# 02_Mcu.net
KiCad netlist of a schematic drawn in Altium Designer
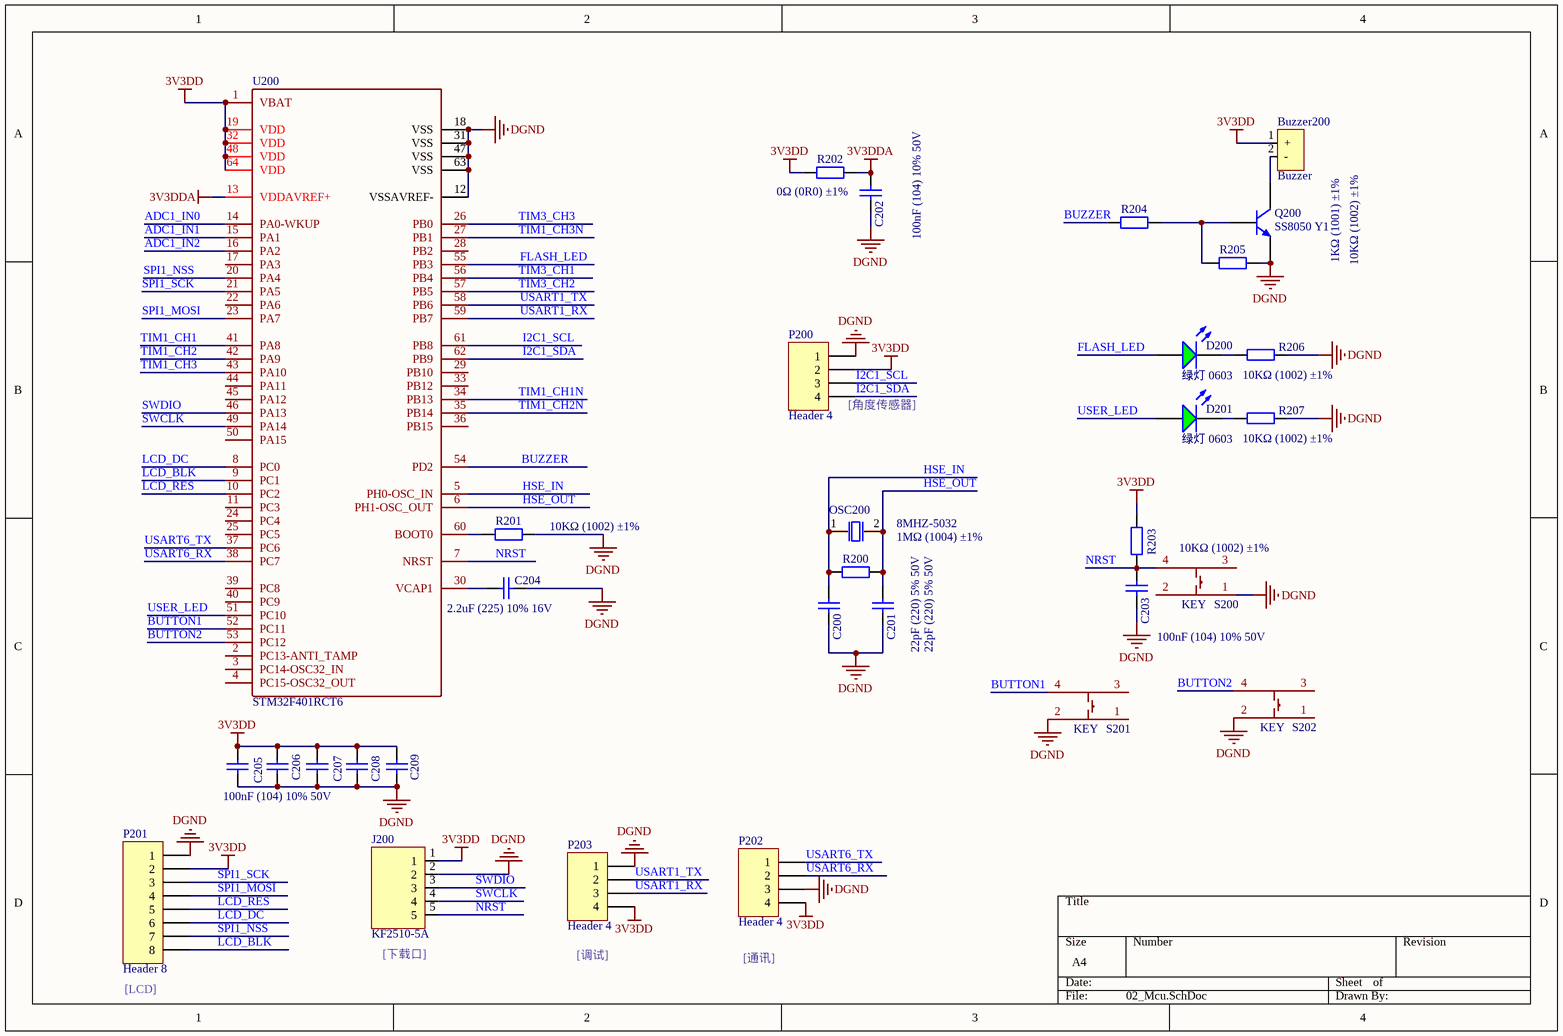
[diagram p0: 02_Mcu.SchDoc]

(export (version "E")
  (design (tool "Eeschema 10.0.6"))
  (components
    (comp (ref "Buzzer200")
      (value "Buzzer")
      (footprint "buzzer-0905")
      (libsource (lib "Schlibv2") (part "Buzzer"))
    )
    (comp (ref "C200")
      (value "22pF (220) 5% 50V")
      (footprint "0603_C")
      (description "贴片电容")
      (libsource (lib "Miscellaneous Devices LC") (part "0603 22pF (220) 5% 50V"))
    )
    (comp (ref "C201")
      (value "22pF (220) 5% 50V")
      (footprint "0603_C")
      (description "贴片电容")
      (libsource (lib "Miscellaneous Devices LC") (part "0603 22pF (220) 5% 50V"))
    )
    (comp (ref "C202")
      (value "100nF (104) 10% 50V")
      (footprint "0603_C")
      (description "贴片电容")
      (libsource (lib "Miscellaneous Devices LC") (part "0603 100nF (104) 10% 50V"))
    )
    (comp (ref "C203")
      (value "100nF (104) 10% 50V")
      (footprint "0603_C")
      (description "贴片电容")
      (libsource (lib "Miscellaneous Devices LC") (part "0603 100nF (104) 10% 50V"))
    )
    (comp (ref "C204")
      (value "2.2uF (225) 10% 16V")
      (footprint "0603_C")
      (description "贴片电容")
      (libsource (lib "Miscellaneous Devices LC") (part "0603 2.2uF (225) 10% 16V"))
    )
    (comp (ref "C205")
      (value "100nF (104) 10% 50V")
      (footprint "LC-0603_C")
      (description "贴片电容")
      (libsource (lib "Miscellaneous Devices LC") (part "0603 100nF (104) 10% 50V"))
    )
    (comp (ref "C206")
      (value "100nF (104) 10% 50V")
      (footprint "LC-0603_C")
      (description "贴片电容")
      (libsource (lib "Miscellaneous Devices LC") (part "0603 100nF (104) 10% 50V"))
    )
    (comp (ref "C207")
      (value "100nF (104) 10% 50V")
      (footprint "LC-0603_C")
      (description "贴片电容")
      (libsource (lib "Miscellaneous Devices LC") (part "0603 100nF (104) 10% 50V"))
    )
    (comp (ref "C208")
      (value "100nF (104) 10% 50V")
      (footprint "LC-0603_C")
      (description "贴片电容")
      (libsource (lib "Miscellaneous Devices LC") (part "0603 100nF (104) 10% 50V"))
    )
    (comp (ref "C209")
      (value "100nF (104) 10% 50V")
      (footprint "LC-0603_C")
      (description "贴片电容")
      (libsource (lib "Miscellaneous Devices LC") (part "0603 100nF (104) 10% 50V"))
    )
    (comp (ref "D200")
      (value "绿灯 0603")
      (footprint "0603_LED_S1")
      (description "发光二极管")
      (libsource (lib "Miscellaneous Devices LC") (part "0603 绿灯"))
    )
    (comp (ref "D201")
      (value "绿灯 0603")
      (footprint "0603_LED_S1")
      (description "发光二极管")
      (libsource (lib "Miscellaneous Devices LC") (part "0603 绿灯"))
    )
    (comp (ref "J200")
      (value "KF2510-5A")
      (footprint "KF2510-5A")
      (libsource (lib "Schlibv2") (part "KF2510-5A"))
    )
    (comp (ref "OSC200")
      (value "8MHZ-5032")
      (footprint "8MHZ-5032")
      (libsource (lib "Schlibv2") (part "8MHZ-5032"))
    )
    (comp (ref "P200")
      (value "Header 4")
      (footprint "HDR1X4")
      (description "Header, 4-Pin")
      (fields (field (name "PUBLISHER") "Altium Limited"))
      (libsource (lib "Miscellaneous Connectors") (part "Header 4"))
    )
    (comp (ref "P201")
      (value "Header 8")
      (footprint "HDR1X8")
      (description "Header, 8-Pin")
      (fields (field (name "PUBLISHER") "Altium Limited"))
      (libsource (lib "Miscellaneous Connectors") (part "Header 8"))
    )
    (comp (ref "P202")
      (value "Header 4")
      (footprint "HDR1X4")
      (description "Header, 4-Pin")
      (fields (field (name "PUBLISHER") "Altium Limited"))
      (libsource (lib "Miscellaneous Connectors") (part "Header 4"))
    )
    (comp (ref "P203")
      (value "Header 4")
      (footprint "HDR1X4")
      (description "Header, 4-Pin")
      (fields (field (name "PUBLISHER") "Altium Limited"))
      (libsource (lib "Miscellaneous Connectors") (part "Header 4"))
    )
    (comp (ref "Q200")
      (value "SS8050 Y1")
      (footprint "SOT-23(SOT-23-3)")
      (description "三极管")
      (libsource (lib "Miscellaneous Devices LC") (part "SOT-23 SS8050 Y1"))
    )
    (comp (ref "R200")
      (value "1MΩ (1004) ±1%")
      (footprint "0603_R")
      (description "贴片电阻")
      (libsource (lib "Miscellaneous Devices LC") (part "0603 1MΩ (1004) 1%"))
    )
    (comp (ref "R201")
      (value "10KΩ (1002) ±1%")
      (footprint "0603_R")
      (description "贴片电阻")
      (libsource (lib "") (part "0603 10KΩ (1002) 1%_1"))
    )
    (comp (ref "R202")
      (value "0Ω (0R0) ±1%")
      (footprint "0603_R")
      (description "贴片电阻")
      (libsource (lib "Miscellaneous Devices LC") (part "0603 0Ω (0R0) 1%"))
    )
    (comp (ref "R203")
      (value "10KΩ (1002) ±1%")
      (footprint "0603_R")
      (description "贴片电阻")
      (libsource (lib "Miscellaneous Devices LC") (part "0603 10KΩ (1002) 1%"))
    )
    (comp (ref "R204")
      (value "1KΩ (1001) ±1%")
      (footprint "0603_R")
      (description "贴片电阻")
      (libsource (lib "Miscellaneous Devices LC") (part "0603 1KΩ (1001) 1%"))
    )
    (comp (ref "R205")
      (value "10KΩ (1002) ±1%")
      (footprint "0603_R")
      (description "贴片电阻")
      (libsource (lib "") (part "0603 10KΩ (1002) 1%_1"))
    )
    (comp (ref "R206")
      (value "10KΩ (1002) ±1%")
      (footprint "0603_R")
      (description "贴片电阻")
      (libsource (lib "") (part "0603 10KΩ (1002) 1%_1"))
    )
    (comp (ref "R207")
      (value "10KΩ (1002) ±1%")
      (footprint "0603_R")
      (description "贴片电阻")
      (libsource (lib "") (part "0603 10KΩ (1002) 1%_1"))
    )
    (comp (ref "S200")
      (value "KEY")
      (footprint "KEY_WHITE")
      (description "白色方块")
      (libsource (lib "Schlibv2") (part "KEY"))
    )
    (comp (ref "S201")
      (value "KEY")
      (footprint "KEY_WHITE")
      (description "白色方块")
      (libsource (lib "Schlibv2") (part "KEY"))
    )
    (comp (ref "S202")
      (value "KEY")
      (footprint "KEY_WHITE")
      (description "白色方块")
      (libsource (lib "Schlibv2") (part "KEY"))
    )
    (comp (ref "U200")
      (value "STM32F401RCT6")
      (footprint "STM32F401RCT6")
      (libsource (lib "Schlibv2") (part "STM32F401RCT6"))
    )
  )
  (nets
    (net (code "1") (name "/ADC1_IN0") (class "Default")
      (node (ref "U200") (pin "14") (pinfunction "PA0-WKUP_14") (pintype "passive"))
    )
    (net (code "2") (name "/ADC1_IN1") (class "Default")
      (node (ref "U200") (pin "15") (pinfunction "PA1_15") (pintype "passive"))
    )
    (net (code "3") (name "/ADC1_IN2") (class "Default")
      (node (ref "U200") (pin "16") (pinfunction "PA2_16") (pintype "passive"))
    )
    (net (code "4") (name "/BUTTON1") (class "Default")
      (node (ref "S201") (pin "4") (pinfunction "4_4") (pintype "passive"))
      (node (ref "U200") (pin "52") (pinfunction "PC11_52") (pintype "passive"))
    )
    (net (code "5") (name "/BUTTON2") (class "Default")
      (node (ref "S202") (pin "4") (pinfunction "4_4") (pintype "passive"))
      (node (ref "U200") (pin "53") (pinfunction "PC12_53") (pintype "passive"))
    )
    (net (code "6") (name "/BUZZER") (class "Default")
      (node (ref "R204") (pin "1") (pinfunction "1_1") (pintype "passive"))
      (node (ref "U200") (pin "54") (pinfunction "PD2_54") (pintype "passive"))
    )
    (net (code "7") (name "/FLASH_LED") (class "Default")
      (node (ref "D200") (pin "A") (pinfunction "A_A") (pintype "passive"))
      (node (ref "U200") (pin "55") (pinfunction "PB3_55") (pintype "passive"))
    )
    (net (code "8") (name "/HSE_IN") (class "Default")
      (node (ref "C200") (pin "2") (pinfunction "2_2") (pintype "passive"))
      (node (ref "OSC200") (pin "1") (pinfunction "OSC1_1") (pintype "passive"))
      (node (ref "R200") (pin "1") (pinfunction "1_1") (pintype "passive"))
      (node (ref "U200") (pin "5") (pinfunction "PH0-OSC_IN_5") (pintype "passive"))
    )
    (net (code "9") (name "/HSE_OUT") (class "Default")
      (node (ref "C201") (pin "2") (pinfunction "2_2") (pintype "passive"))
      (node (ref "OSC200") (pin "2") (pinfunction "OSC2_2") (pintype "passive"))
      (node (ref "R200") (pin "2") (pinfunction "2_2") (pintype "passive"))
      (node (ref "U200") (pin "6") (pinfunction "PH1-OSC_OUT_6") (pintype "passive"))
    )
    (net (code "10") (name "/I2C1_SCL") (class "Default")
      (node (ref "P200") (pin "3") (pinfunction "3_3") (pintype "passive"))
      (node (ref "U200") (pin "61") (pinfunction "PB8_61") (pintype "passive"))
    )
    (net (code "11") (name "/I2C1_SDA") (class "Default")
      (node (ref "P200") (pin "4") (pinfunction "4_4") (pintype "passive"))
      (node (ref "U200") (pin "62") (pinfunction "PB9_62") (pintype "passive"))
    )
    (net (code "12") (name "/LCD_BLK") (class "Default")
      (node (ref "P201") (pin "8") (pinfunction "8_8") (pintype "passive"))
      (node (ref "U200") (pin "9") (pinfunction "PC1_9") (pintype "passive"))
    )
    (net (code "13") (name "/LCD_DC") (class "Default")
      (node (ref "P201") (pin "6") (pinfunction "6_6") (pintype "passive"))
      (node (ref "U200") (pin "8") (pinfunction "PC0_8") (pintype "passive"))
    )
    (net (code "14") (name "/LCD_RES") (class "Default")
      (node (ref "P201") (pin "5") (pinfunction "5_5") (pintype "passive"))
      (node (ref "U200") (pin "10") (pinfunction "PC2_10") (pintype "passive"))
    )
    (net (code "15") (name "/NRST") (class "Default")
      (node (ref "C203") (pin "2") (pinfunction "2_2") (pintype "passive"))
      (node (ref "J200") (pin "5") (pinfunction "5_5") (pintype "passive"))
      (node (ref "R203") (pin "1") (pinfunction "1_1") (pintype "passive"))
      (node (ref "S200") (pin "4") (pinfunction "4_4") (pintype "passive"))
      (node (ref "U200") (pin "7") (pinfunction "NRST_7") (pintype "passive"))
    )
    (net (code "16") (name "/SPI1_MOSI") (class "Default")
      (node (ref "P201") (pin "4") (pinfunction "4_4") (pintype "passive"))
      (node (ref "U200") (pin "23") (pinfunction "PA7_23") (pintype "passive"))
    )
    (net (code "17") (name "/SPI1_NSS") (class "Default")
      (node (ref "P201") (pin "7") (pinfunction "7_7") (pintype "passive"))
      (node (ref "U200") (pin "20") (pinfunction "PA4_20") (pintype "passive"))
    )
    (net (code "18") (name "/SPI1_SCK") (class "Default")
      (node (ref "P201") (pin "3") (pinfunction "3_3") (pintype "passive"))
      (node (ref "U200") (pin "21") (pinfunction "PA5_21") (pintype "passive"))
    )
    (net (code "19") (name "/SWCLK") (class "Default")
      (node (ref "J200") (pin "4") (pinfunction "4_4") (pintype "passive"))
      (node (ref "U200") (pin "49") (pinfunction "PA14_49") (pintype "passive"))
    )
    (net (code "20") (name "/SWDIO") (class "Default")
      (node (ref "J200") (pin "3") (pinfunction "3_3") (pintype "passive"))
      (node (ref "U200") (pin "46") (pinfunction "PA13_46") (pintype "passive"))
    )
    (net (code "21") (name "/TIM1_CH1") (class "Default")
      (node (ref "U200") (pin "41") (pinfunction "PA8_41") (pintype "passive"))
    )
    (net (code "22") (name "/TIM1_CH1N") (class "Default")
      (node (ref "U200") (pin "34") (pinfunction "PB13_34") (pintype "passive"))
    )
    (net (code "23") (name "/TIM1_CH2") (class "Default")
      (node (ref "U200") (pin "42") (pinfunction "PA9_42") (pintype "passive"))
    )
    (net (code "24") (name "/TIM1_CH2N") (class "Default")
      (node (ref "U200") (pin "35") (pinfunction "PB14_35") (pintype "passive"))
    )
    (net (code "25") (name "/TIM1_CH3") (class "Default")
      (node (ref "U200") (pin "43") (pinfunction "PA10_43") (pintype "passive"))
    )
    (net (code "26") (name "/TIM1_CH3N") (class "Default")
      (node (ref "U200") (pin "27") (pinfunction "PB1_27") (pintype "passive"))
    )
    (net (code "27") (name "/TIM3_CH1") (class "Default")
      (node (ref "U200") (pin "56") (pinfunction "PB4_56") (pintype "passive"))
    )
    (net (code "28") (name "/TIM3_CH2") (class "Default")
      (node (ref "U200") (pin "57") (pinfunction "PB5_57") (pintype "passive"))
    )
    (net (code "29") (name "/TIM3_CH3") (class "Default")
      (node (ref "U200") (pin "26") (pinfunction "PB0_26") (pintype "passive"))
    )
    (net (code "30") (name "/USART1_RX") (class "Default")
      (node (ref "P203") (pin "3") (pinfunction "3_3") (pintype "passive"))
      (node (ref "U200") (pin "59") (pinfunction "PB7_59") (pintype "passive"))
    )
    (net (code "31") (name "/USART1_TX") (class "Default")
      (node (ref "P203") (pin "2") (pinfunction "2_2") (pintype "passive"))
      (node (ref "U200") (pin "58") (pinfunction "PB6_58") (pintype "passive"))
    )
    (net (code "32") (name "/USART6_RX") (class "Default")
      (node (ref "P202") (pin "2") (pinfunction "2_2") (pintype "passive"))
      (node (ref "U200") (pin "38") (pinfunction "PC7_38") (pintype "passive"))
    )
    (net (code "33") (name "/USART6_TX") (class "Default")
      (node (ref "P202") (pin "1") (pinfunction "1_1") (pintype "passive"))
      (node (ref "U200") (pin "37") (pinfunction "PC6_37") (pintype "passive"))
    )
    (net (code "34") (name "/USER_LED") (class "Default")
      (node (ref "D201") (pin "A") (pinfunction "A_A") (pintype "passive"))
      (node (ref "U200") (pin "51") (pinfunction "PC10_51") (pintype "passive"))
    )
    (net (code "35") (name "3V3DD") (class "Default")
      (node (ref "Buzzer200") (pin "1") (pinfunction "+_1") (pintype "passive"))
      (node (ref "C205") (pin "2") (pinfunction "2_2") (pintype "passive"))
      (node (ref "C206") (pin "2") (pinfunction "2_2") (pintype "passive"))
      (node (ref "C207") (pin "2") (pinfunction "2_2") (pintype "passive"))
      (node (ref "C208") (pin "2") (pinfunction "2_2") (pintype "passive"))
      (node (ref "C209") (pin "2") (pinfunction "2_2") (pintype "passive"))
      (node (ref "J200") (pin "1") (pinfunction "1_1") (pintype "passive"))
      (node (ref "P200") (pin "2") (pinfunction "2_2") (pintype "passive"))
      (node (ref "P201") (pin "2") (pinfunction "2_2") (pintype "passive"))
      (node (ref "P202") (pin "4") (pinfunction "4_4") (pintype "passive"))
      (node (ref "P203") (pin "4") (pinfunction "4_4") (pintype "passive"))
      (node (ref "R202") (pin "1") (pinfunction "1_1") (pintype "passive"))
      (node (ref "R203") (pin "2") (pinfunction "2_2") (pintype "passive"))
      (node (ref "U200") (pin "1") (pinfunction "VBAT_1") (pintype "passive"))
      (node (ref "U200") (pin "19") (pinfunction "VDD_19") (pintype "passive"))
      (node (ref "U200") (pin "32") (pinfunction "VDD_32") (pintype "passive"))
      (node (ref "U200") (pin "48") (pinfunction "VDD_48") (pintype "passive"))
      (node (ref "U200") (pin "64") (pinfunction "VDD_64") (pintype "passive"))
    )
    (net (code "36") (name "3V3DDA") (class "Default")
      (node (ref "C202") (pin "2") (pinfunction "2_2") (pintype "passive"))
      (node (ref "R202") (pin "2") (pinfunction "2_2") (pintype "passive"))
      (node (ref "U200") (pin "13") (pinfunction "VDDAVREF+_13") (pintype "passive"))
    )
    (net (code "37") (name "DGND") (class "Default")
      (node (ref "C200") (pin "1") (pinfunction "1_1") (pintype "passive"))
      (node (ref "C201") (pin "1") (pinfunction "1_1") (pintype "passive"))
      (node (ref "C202") (pin "1") (pinfunction "1_1") (pintype "passive"))
      (node (ref "C203") (pin "1") (pinfunction "1_1") (pintype "passive"))
      (node (ref "C204") (pin "2") (pinfunction "2_2") (pintype "passive"))
      (node (ref "C205") (pin "1") (pinfunction "1_1") (pintype "passive"))
      (node (ref "C206") (pin "1") (pinfunction "1_1") (pintype "passive"))
      (node (ref "C207") (pin "1") (pinfunction "1_1") (pintype "passive"))
      (node (ref "C208") (pin "1") (pinfunction "1_1") (pintype "passive"))
      (node (ref "C209") (pin "1") (pinfunction "1_1") (pintype "passive"))
      (node (ref "J200") (pin "2") (pinfunction "2_2") (pintype "passive"))
      (node (ref "P200") (pin "1") (pinfunction "1_1") (pintype "passive"))
      (node (ref "P201") (pin "1") (pinfunction "1_1") (pintype "passive"))
      (node (ref "P202") (pin "3") (pinfunction "3_3") (pintype "passive"))
      (node (ref "P203") (pin "1") (pinfunction "1_1") (pintype "passive"))
      (node (ref "Q200") (pin "2") (pinfunction "E_2") (pintype "passive"))
      (node (ref "R201") (pin "2") (pinfunction "2_2") (pintype "passive"))
      (node (ref "R205") (pin "2") (pinfunction "2_2") (pintype "passive"))
      (node (ref "R206") (pin "2") (pinfunction "2_2") (pintype "passive"))
      (node (ref "R207") (pin "2") (pinfunction "2_2") (pintype "passive"))
      (node (ref "S200") (pin "1") (pinfunction "1_1") (pintype "passive"))
      (node (ref "S201") (pin "2") (pinfunction "2_2") (pintype "passive"))
      (node (ref "S202") (pin "2") (pinfunction "2_2") (pintype "passive"))
      (node (ref "U200") (pin "12") (pinfunction "VSSAVREF-_12") (pintype "passive"))
      (node (ref "U200") (pin "18") (pinfunction "VSS_18") (pintype "passive"))
      (node (ref "U200") (pin "31") (pinfunction "VSS_31") (pintype "passive"))
      (node (ref "U200") (pin "47") (pinfunction "VSS_47") (pintype "passive"))
      (node (ref "U200") (pin "63") (pinfunction "VSS_63") (pintype "passive"))
    )
    (net (code "38") (name "Net-(Buzzer200--)") (class "Default")
      (node (ref "Buzzer200") (pin "2") (pinfunction "-_2") (pintype "passive"))
      (node (ref "Q200") (pin "3") (pinfunction "C_3") (pintype "passive"))
    )
    (net (code "39") (name "Net-(D200-PadK)") (class "Default")
      (node (ref "D200") (pin "K") (pinfunction "K_K") (pintype "passive"))
      (node (ref "R206") (pin "1") (pinfunction "1_1") (pintype "passive"))
    )
    (net (code "40") (name "Net-(D201-PadK)") (class "Default")
      (node (ref "D201") (pin "K") (pinfunction "K_K") (pintype "passive"))
      (node (ref "R207") (pin "1") (pinfunction "1_1") (pintype "passive"))
    )
    (net (code "41") (name "Net-(Q200-B)") (class "Default")
      (node (ref "Q200") (pin "1") (pinfunction "B_1") (pintype "passive"))
      (node (ref "R204") (pin "2") (pinfunction "2_2") (pintype "passive"))
      (node (ref "R205") (pin "1") (pinfunction "1_1") (pintype "passive"))
    )
    (net (code "42") (name "Net-(U200-BOOT0)") (class "Default")
      (node (ref "R201") (pin "1") (pinfunction "1_1") (pintype "passive"))
      (node (ref "U200") (pin "60") (pinfunction "BOOT0_60") (pintype "passive"))
    )
    (net (code "43") (name "Net-(U200-VCAP1)") (class "Default")
      (node (ref "C204") (pin "1") (pinfunction "1_1") (pintype "passive"))
      (node (ref "U200") (pin "30") (pinfunction "VCAP1_30") (pintype "passive"))
    )
    (net (code "44") (name "unconnected-(S200-Pad2)") (class "Default")
      (node (ref "S200") (pin "2") (pinfunction "2_2") (pintype "passive"))
    )
    (net (code "45") (name "unconnected-(S200-Pad3)") (class "Default")
      (node (ref "S200") (pin "3") (pinfunction "3_3") (pintype "passive"))
    )
    (net (code "46") (name "unconnected-(S201-Pad1)") (class "Default")
      (node (ref "S201") (pin "1") (pinfunction "1_1") (pintype "passive"))
    )
    (net (code "47") (name "unconnected-(S201-Pad3)") (class "Default")
      (node (ref "S201") (pin "3") (pinfunction "3_3") (pintype "passive"))
    )
    (net (code "48") (name "unconnected-(S202-Pad1)") (class "Default")
      (node (ref "S202") (pin "1") (pinfunction "1_1") (pintype "passive"))
    )
    (net (code "49") (name "unconnected-(S202-Pad3)") (class "Default")
      (node (ref "S202") (pin "3") (pinfunction "3_3") (pintype "passive"))
    )
    (net (code "50") (name "unconnected-(U200-PA3-Pad17)") (class "Default")
      (node (ref "U200") (pin "17") (pinfunction "PA3_17") (pintype "passive"))
    )
    (net (code "51") (name "unconnected-(U200-PA6-Pad22)") (class "Default")
      (node (ref "U200") (pin "22") (pinfunction "PA6_22") (pintype "passive"))
    )
    (net (code "52") (name "unconnected-(U200-PA11-Pad44)") (class "Default")
      (node (ref "U200") (pin "44") (pinfunction "PA11_44") (pintype "passive"))
    )
    (net (code "53") (name "unconnected-(U200-PA12-Pad45)") (class "Default")
      (node (ref "U200") (pin "45") (pinfunction "PA12_45") (pintype "passive"))
    )
    (net (code "54") (name "unconnected-(U200-PA15-Pad50)") (class "Default")
      (node (ref "U200") (pin "50") (pinfunction "PA15_50") (pintype "passive"))
    )
    (net (code "55") (name "unconnected-(U200-PB2-Pad28)") (class "Default")
      (node (ref "U200") (pin "28") (pinfunction "PB2_28") (pintype "passive"))
    )
    (net (code "56") (name "unconnected-(U200-PB10-Pad29)") (class "Default")
      (node (ref "U200") (pin "29") (pinfunction "PB10_29") (pintype "passive"))
    )
    (net (code "57") (name "unconnected-(U200-PB12-Pad33)") (class "Default")
      (node (ref "U200") (pin "33") (pinfunction "PB12_33") (pintype "passive"))
    )
    (net (code "58") (name "unconnected-(U200-PB15-Pad36)") (class "Default")
      (node (ref "U200") (pin "36") (pinfunction "PB15_36") (pintype "passive"))
    )
    (net (code "59") (name "unconnected-(U200-PC3-Pad11)") (class "Default")
      (node (ref "U200") (pin "11") (pinfunction "PC3_11") (pintype "passive"))
    )
    (net (code "60") (name "unconnected-(U200-PC4-Pad24)") (class "Default")
      (node (ref "U200") (pin "24") (pinfunction "PC4_24") (pintype "passive"))
    )
    (net (code "61") (name "unconnected-(U200-PC5-Pad25)") (class "Default")
      (node (ref "U200") (pin "25") (pinfunction "PC5_25") (pintype "passive"))
    )
    (net (code "62") (name "unconnected-(U200-PC8-Pad39)") (class "Default")
      (node (ref "U200") (pin "39") (pinfunction "PC8_39") (pintype "passive"))
    )
    (net (code "63") (name "unconnected-(U200-PC9-Pad40)") (class "Default")
      (node (ref "U200") (pin "40") (pinfunction "PC9_40") (pintype "passive"))
    )
    (net (code "64") (name "unconnected-(U200-PC13-ANTI_TAMP-Pad2)") (class "Default")
      (node (ref "U200") (pin "2") (pinfunction "PC13-ANTI_TAMP_2") (pintype "passive"))
    )
    (net (code "65") (name "unconnected-(U200-PC14-OSC32_IN-Pad3)") (class "Default")
      (node (ref "U200") (pin "3") (pinfunction "PC14-OSC32_IN_3") (pintype "passive"))
    )
    (net (code "66") (name "unconnected-(U200-PC15-OSC32_OUT-Pad4)") (class "Default")
      (node (ref "U200") (pin "4") (pinfunction "PC15-OSC32_OUT_4") (pintype "passive"))
    )
  )
)
